# kachisys.net
KiCad netlist of a schematic drawn in EAGLE
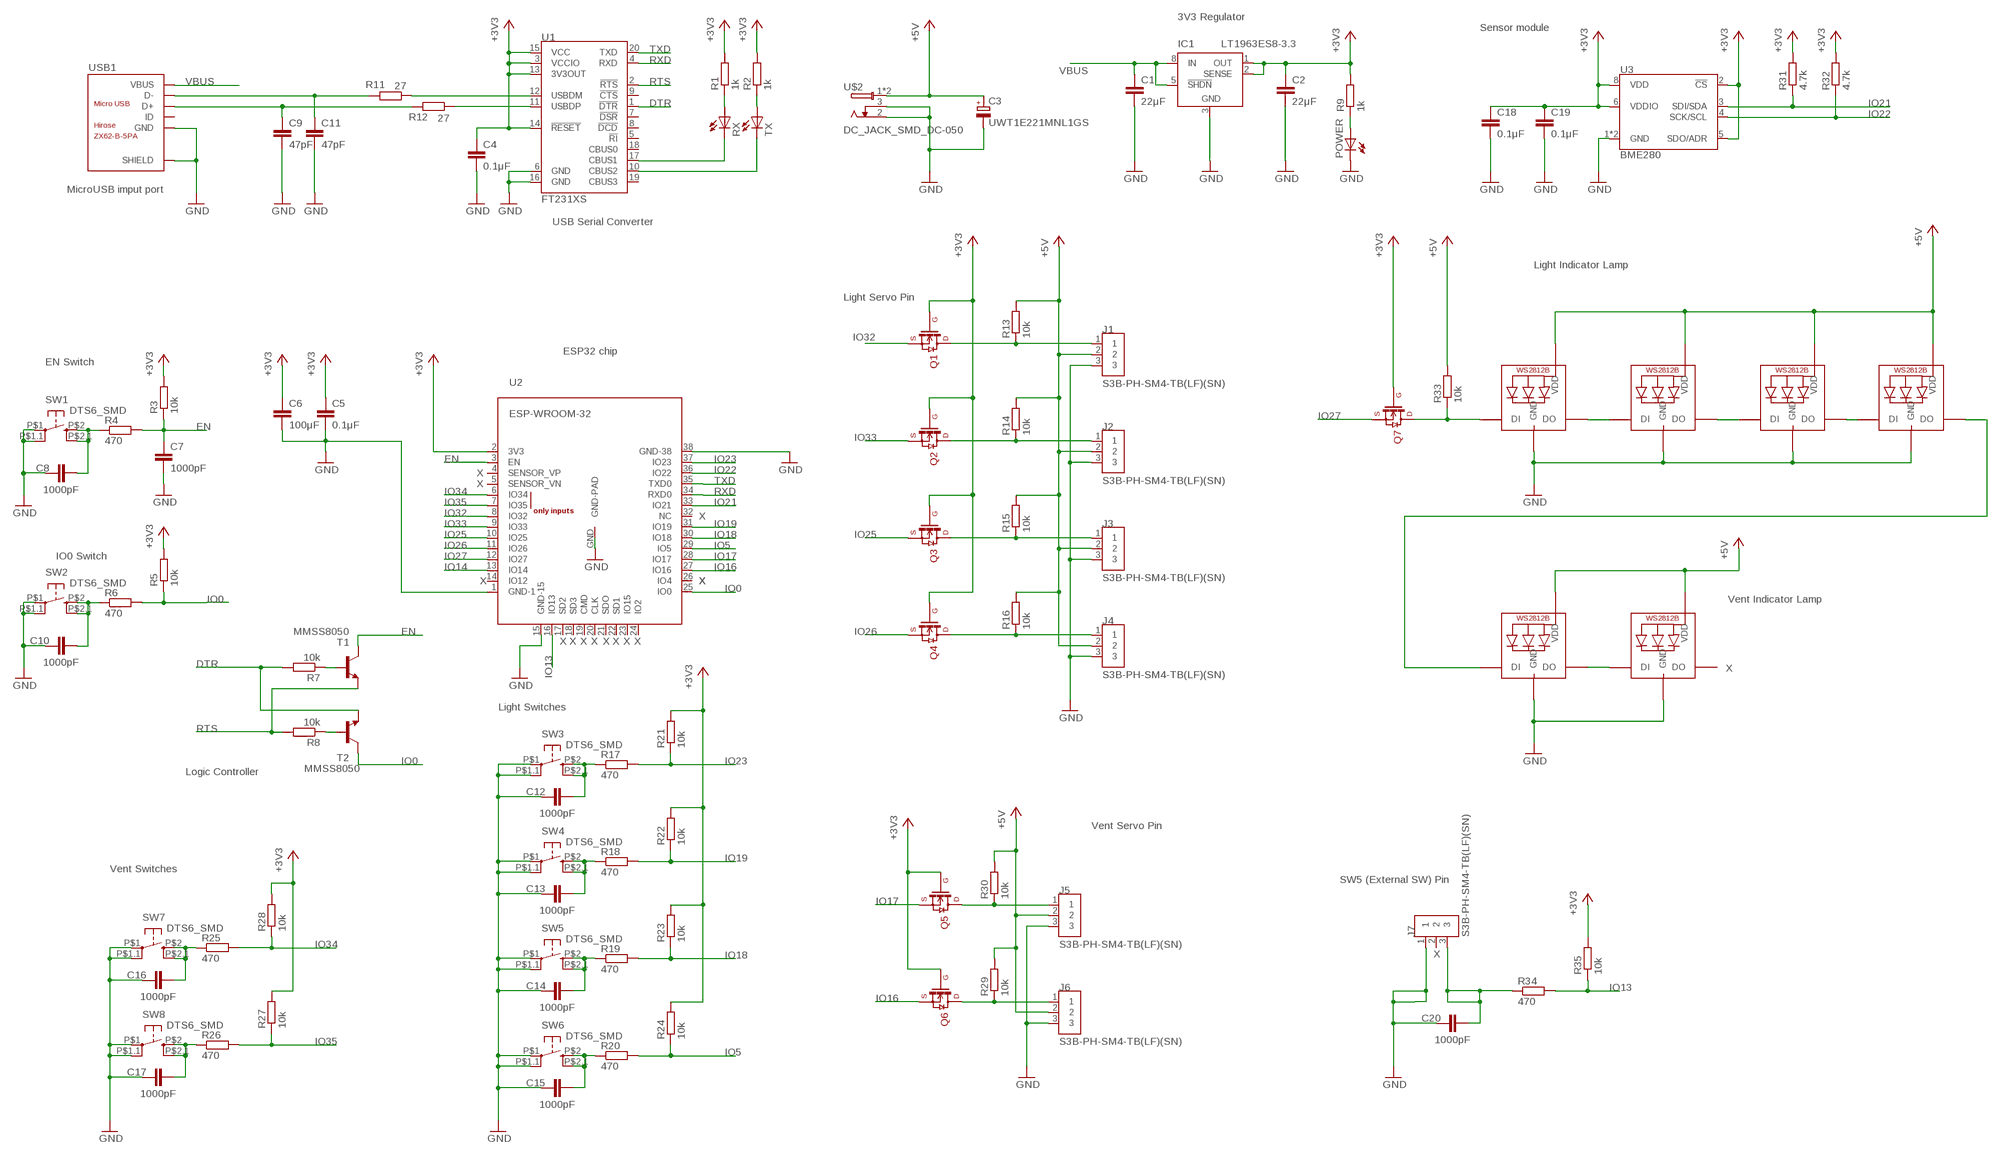
[diagram p0: schematic, sheet 1]

(export (version "E")
  (design (tool "Eeschema 10.0.6"))
  (components
    (comp (ref "C1")
      (value "22μF")
      (footprint "eagle-import:C2012")
      (libsource (lib "eagle-import") (part "resistor_348_C-EUC2012"))
    )
    (comp (ref "C2")
      (value "22μF")
      (footprint "eagle-import:C2012")
      (libsource (lib "eagle-import") (part "resistor_348_C-EUC2012"))
    )
    (comp (ref "C3")
      (value "UWT1E221MNL1GS")
      (footprint "eagle-import:NICHICON-ALMINUM-CAPACITOR-8MM")
      (libsource (lib "eagle-import") (part "UWT1E221MNL1GS"))
    )
    (comp (ref "C4")
      (value "0.1μF")
      (footprint "eagle-import:C0603")
      (libsource (lib "eagle-import") (part "resistor_348_C-EUC0603"))
    )
    (comp (ref "C5")
      (value "0.1μF")
      (footprint "eagle-import:C0603")
      (libsource (lib "eagle-import") (part "resistor_348_C-EUC0603"))
    )
    (comp (ref "C6")
      (value "100μF")
      (footprint "eagle-import:C3225")
      (libsource (lib "eagle-import") (part "resistor_348_C-EUC3225"))
    )
    (comp (ref "C7")
      (value "1000pF")
      (footprint "eagle-import:C0603")
      (libsource (lib "eagle-import") (part "resistor_348_C-EUC0603"))
    )
    (comp (ref "C8")
      (value "1000pF")
      (footprint "eagle-import:C0603")
      (libsource (lib "eagle-import") (part "resistor_348_C-EUC0603"))
    )
    (comp (ref "C9")
      (value "47pF")
      (footprint "eagle-import:C1608")
      (libsource (lib "eagle-import") (part "C-EUC1608"))
    )
    (comp (ref "C10")
      (value "1000pF")
      (footprint "eagle-import:C0603")
      (libsource (lib "eagle-import") (part "resistor_348_C-EUC0603"))
    )
    (comp (ref "C11")
      (value "47pF")
      (footprint "eagle-import:C1608")
      (libsource (lib "eagle-import") (part "C-EUC1608"))
    )
    (comp (ref "C12")
      (value "1000pF")
      (footprint "eagle-import:C0603")
      (libsource (lib "eagle-import") (part "resistor_348_C-EUC0603"))
    )
    (comp (ref "C13")
      (value "1000pF")
      (footprint "eagle-import:C0603")
      (libsource (lib "eagle-import") (part "resistor_348_C-EUC0603"))
    )
    (comp (ref "C14")
      (value "1000pF")
      (footprint "eagle-import:C0603")
      (libsource (lib "eagle-import") (part "resistor_348_C-EUC0603"))
    )
    (comp (ref "C15")
      (value "1000pF")
      (footprint "eagle-import:C0603")
      (libsource (lib "eagle-import") (part "resistor_348_C-EUC0603"))
    )
    (comp (ref "C16")
      (value "1000pF")
      (footprint "eagle-import:C0603")
      (libsource (lib "eagle-import") (part "resistor_348_C-EUC0603"))
    )
    (comp (ref "C17")
      (value "1000pF")
      (footprint "eagle-import:C0603")
      (libsource (lib "eagle-import") (part "resistor_348_C-EUC0603"))
    )
    (comp (ref "C18")
      (value "0.1μF")
      (footprint "eagle-import:C0603")
      (libsource (lib "eagle-import") (part "resistor_348_C-EUC0603"))
    )
    (comp (ref "C19")
      (value "0.1μF")
      (footprint "eagle-import:C0603")
      (libsource (lib "eagle-import") (part "resistor_348_C-EUC0603"))
    )
    (comp (ref "C20")
      (value "1000pF")
      (footprint "eagle-import:C0603")
      (libsource (lib "eagle-import") (part "resistor_348_C-EUC0603"))
    )
    (comp (ref "IC1")
      (value "LT1963ES8-3.3")
      (footprint "eagle-import:SOIC8")
      (libsource (lib "eagle-import") (part "LT1963ES8-3.3"))
    )
    (comp (ref "J1")
      (value "S3B-PH-SM4-TB(LF)(SN)")
      (footprint "eagle-import:JST_S3B-PH-SM4-TB(LF)(SN)")
      (fields
        (field (name "DIGI-KEY_PART_NUMBER") "455-1750-1-ND")
        (field (name "MF") "JST Sales")
        (field (name "MP") "S3B-PH-SM4-TB_LF__SN_")
      )
      (libsource (lib "eagle-import") (part "S3B-PH-SM4-TB(LF)(SN)"))
    )
    (comp (ref "J2")
      (value "S3B-PH-SM4-TB(LF)(SN)")
      (footprint "eagle-import:JST_S3B-PH-SM4-TB(LF)(SN)")
      (fields
        (field (name "DIGI-KEY_PART_NUMBER") "455-1750-1-ND")
        (field (name "MF") "JST Sales")
        (field (name "MP") "S3B-PH-SM4-TB_LF__SN_")
      )
      (libsource (lib "eagle-import") (part "S3B-PH-SM4-TB(LF)(SN)"))
    )
    (comp (ref "J3")
      (value "S3B-PH-SM4-TB(LF)(SN)")
      (footprint "eagle-import:JST_S3B-PH-SM4-TB(LF)(SN)")
      (fields
        (field (name "DIGI-KEY_PART_NUMBER") "455-1750-1-ND")
        (field (name "MF") "JST Sales")
        (field (name "MP") "S3B-PH-SM4-TB_LF__SN_")
      )
      (libsource (lib "eagle-import") (part "S3B-PH-SM4-TB(LF)(SN)"))
    )
    (comp (ref "J4")
      (value "S3B-PH-SM4-TB(LF)(SN)")
      (footprint "eagle-import:JST_S3B-PH-SM4-TB(LF)(SN)")
      (fields
        (field (name "DIGI-KEY_PART_NUMBER") "455-1750-1-ND")
        (field (name "MF") "JST Sales")
        (field (name "MP") "S3B-PH-SM4-TB_LF__SN_")
      )
      (libsource (lib "eagle-import") (part "S3B-PH-SM4-TB(LF)(SN)"))
    )
    (comp (ref "J5")
      (value "S3B-PH-SM4-TB(LF)(SN)")
      (footprint "eagle-import:JST_S3B-PH-SM4-TB(LF)(SN)")
      (fields
        (field (name "DIGI-KEY_PART_NUMBER") "455-1750-1-ND")
        (field (name "MF") "JST Sales")
        (field (name "MP") "S3B-PH-SM4-TB_LF__SN_")
      )
      (libsource (lib "eagle-import") (part "S3B-PH-SM4-TB(LF)(SN)"))
    )
    (comp (ref "J6")
      (value "S3B-PH-SM4-TB(LF)(SN)")
      (footprint "eagle-import:JST_S3B-PH-SM4-TB(LF)(SN)")
      (fields
        (field (name "DIGI-KEY_PART_NUMBER") "455-1750-1-ND")
        (field (name "MF") "JST Sales")
        (field (name "MP") "S3B-PH-SM4-TB_LF__SN_")
      )
      (libsource (lib "eagle-import") (part "S3B-PH-SM4-TB(LF)(SN)"))
    )
    (comp (ref "J7")
      (value "S3B-PH-SM4-TB(LF)(SN)")
      (footprint "eagle-import:JST_S3B-PH-SM4-TB(LF)(SN)")
      (fields
        (field (name "DIGI-KEY_PART_NUMBER") "455-1750-1-ND")
        (field (name "MF") "JST Sales")
        (field (name "MP") "S3B-PH-SM4-TB_LF__SN_")
      )
      (libsource (lib "eagle-import") (part "S3B-PH-SM4-TB(LF)(SN)"))
    )
    (comp (ref "LED1")
      (value "WS2812B_5050N")
      (footprint "eagle-import:WS2812B-NARROW")
      (libsource (lib "eagle-import") (part "WS2812B_5050N"))
    )
    (comp (ref "LED2")
      (value "WS2812B_5050N")
      (footprint "eagle-import:WS2812B-NARROW")
      (libsource (lib "eagle-import") (part "WS2812B_5050N"))
    )
    (comp (ref "LED3")
      (value "WS2812B_5050N")
      (footprint "eagle-import:WS2812B-NARROW")
      (libsource (lib "eagle-import") (part "WS2812B_5050N"))
    )
    (comp (ref "LED4")
      (value "WS2812B_5050N")
      (footprint "eagle-import:WS2812B-NARROW")
      (libsource (lib "eagle-import") (part "WS2812B_5050N"))
    )
    (comp (ref "LED5")
      (value "WS2812B_5050N")
      (footprint "eagle-import:WS2812B-NARROW")
      (libsource (lib "eagle-import") (part "WS2812B_5050N"))
    )
    (comp (ref "LED6")
      (value "WS2812B_5050N")
      (footprint "eagle-import:WS2812B-NARROW")
      (libsource (lib "eagle-import") (part "WS2812B_5050N"))
    )
    (comp (ref "POWER")
      (value "LEDCHIP-LED0603")
      (footprint "eagle-import:CHIP-LED0603")
      (libsource (lib "eagle-import") (part "LEDCHIP-LED0603"))
    )
    (comp (ref "Q1")
      (value "BSS138")
      (footprint "eagle-import:SOT-23")
      (libsource (lib "eagle-import") (part "BSS138"))
    )
    (comp (ref "Q2")
      (value "BSS138")
      (footprint "eagle-import:SOT-23")
      (libsource (lib "eagle-import") (part "BSS138"))
    )
    (comp (ref "Q3")
      (value "BSS138")
      (footprint "eagle-import:SOT-23")
      (libsource (lib "eagle-import") (part "BSS138"))
    )
    (comp (ref "Q4")
      (value "BSS138")
      (footprint "eagle-import:SOT-23")
      (libsource (lib "eagle-import") (part "BSS138"))
    )
    (comp (ref "Q5")
      (value "BSS138")
      (footprint "eagle-import:SOT-23")
      (libsource (lib "eagle-import") (part "BSS138"))
    )
    (comp (ref "Q6")
      (value "BSS138")
      (footprint "eagle-import:SOT-23")
      (libsource (lib "eagle-import") (part "BSS138"))
    )
    (comp (ref "Q7")
      (value "BSS138")
      (footprint "eagle-import:SOT-23")
      (libsource (lib "eagle-import") (part "BSS138"))
    )
    (comp (ref "R1")
      (value "1k")
      (footprint "eagle-import:R0603")
      (libsource (lib "eagle-import") (part "R-EU_R0603"))
    )
    (comp (ref "R2")
      (value "1k")
      (footprint "eagle-import:R0603")
      (libsource (lib "eagle-import") (part "R-EU_R0603"))
    )
    (comp (ref "R3")
      (value "10k")
      (footprint "eagle-import:R0603")
      (libsource (lib "eagle-import") (part "R-EU_R0603"))
    )
    (comp (ref "R4")
      (value "470")
      (footprint "eagle-import:R0603")
      (libsource (lib "eagle-import") (part "R-EU_R0603"))
    )
    (comp (ref "R5")
      (value "10k")
      (footprint "eagle-import:R0603")
      (libsource (lib "eagle-import") (part "R-EU_R0603"))
    )
    (comp (ref "R6")
      (value "470")
      (footprint "eagle-import:R0603")
      (libsource (lib "eagle-import") (part "R-EU_R0603"))
    )
    (comp (ref "R7")
      (value "10k")
      (footprint "eagle-import:R0603")
      (libsource (lib "eagle-import") (part "R-EU_R0603"))
    )
    (comp (ref "R8")
      (value "10k")
      (footprint "eagle-import:R0603")
      (libsource (lib "eagle-import") (part "R-EU_R0603"))
    )
    (comp (ref "R9")
      (value "1k")
      (footprint "eagle-import:R0603")
      (libsource (lib "eagle-import") (part "R-EU_R0603"))
    )
    (comp (ref "R11")
      (value "27")
      (footprint "eagle-import:R0603")
      (libsource (lib "eagle-import") (part "R-EU_R0603"))
    )
    (comp (ref "R12")
      (value "27")
      (footprint "eagle-import:R0603")
      (libsource (lib "eagle-import") (part "R-EU_R0603"))
    )
    (comp (ref "R13")
      (value "10k")
      (footprint "eagle-import:R0603")
      (libsource (lib "eagle-import") (part "R-EU_R0603"))
    )
    (comp (ref "R14")
      (value "10k")
      (footprint "eagle-import:R0603")
      (libsource (lib "eagle-import") (part "R-EU_R0603"))
    )
    (comp (ref "R15")
      (value "10k")
      (footprint "eagle-import:R0603")
      (libsource (lib "eagle-import") (part "R-EU_R0603"))
    )
    (comp (ref "R16")
      (value "10k")
      (footprint "eagle-import:R0603")
      (libsource (lib "eagle-import") (part "R-EU_R0603"))
    )
    (comp (ref "R17")
      (value "470")
      (footprint "eagle-import:R0603")
      (libsource (lib "eagle-import") (part "R-EU_R0603"))
    )
    (comp (ref "R18")
      (value "470")
      (footprint "eagle-import:R0603")
      (libsource (lib "eagle-import") (part "R-EU_R0603"))
    )
    (comp (ref "R19")
      (value "470")
      (footprint "eagle-import:R0603")
      (libsource (lib "eagle-import") (part "R-EU_R0603"))
    )
    (comp (ref "R20")
      (value "470")
      (footprint "eagle-import:R0603")
      (libsource (lib "eagle-import") (part "R-EU_R0603"))
    )
    (comp (ref "R21")
      (value "10k")
      (footprint "eagle-import:R0603")
      (libsource (lib "eagle-import") (part "R-EU_R0603"))
    )
    (comp (ref "R22")
      (value "10k")
      (footprint "eagle-import:R0603")
      (libsource (lib "eagle-import") (part "R-EU_R0603"))
    )
    (comp (ref "R23")
      (value "10k")
      (footprint "eagle-import:R0603")
      (libsource (lib "eagle-import") (part "R-EU_R0603"))
    )
    (comp (ref "R24")
      (value "10k")
      (footprint "eagle-import:R0603")
      (libsource (lib "eagle-import") (part "R-EU_R0603"))
    )
    (comp (ref "R25")
      (value "470")
      (footprint "eagle-import:R0603")
      (libsource (lib "eagle-import") (part "R-EU_R0603"))
    )
    (comp (ref "R26")
      (value "470")
      (footprint "eagle-import:R0603")
      (libsource (lib "eagle-import") (part "R-EU_R0603"))
    )
    (comp (ref "R27")
      (value "10k")
      (footprint "eagle-import:R0603")
      (libsource (lib "eagle-import") (part "R-EU_R0603"))
    )
    (comp (ref "R28")
      (value "10k")
      (footprint "eagle-import:R0603")
      (libsource (lib "eagle-import") (part "R-EU_R0603"))
    )
    (comp (ref "R29")
      (value "10k")
      (footprint "eagle-import:R0603")
      (libsource (lib "eagle-import") (part "R-EU_R0603"))
    )
    (comp (ref "R30")
      (value "10k")
      (footprint "eagle-import:R0603")
      (libsource (lib "eagle-import") (part "R-EU_R0603"))
    )
    (comp (ref "R31")
      (value "4.7k")
      (footprint "eagle-import:R0603")
      (libsource (lib "eagle-import") (part "R-EU_R0603"))
    )
    (comp (ref "R32")
      (value "4.7k")
      (footprint "eagle-import:R0603")
      (libsource (lib "eagle-import") (part "R-EU_R0603"))
    )
    (comp (ref "R33")
      (value "10k")
      (footprint "eagle-import:R0603")
      (libsource (lib "eagle-import") (part "R-EU_R0603"))
    )
    (comp (ref "R34")
      (value "470")
      (footprint "eagle-import:R0603")
      (libsource (lib "eagle-import") (part "R-EU_R0603"))
    )
    (comp (ref "R35")
      (value "10k")
      (footprint "eagle-import:R0603")
      (libsource (lib "eagle-import") (part "R-EU_R0603"))
    )
    (comp (ref "RX")
      (value "LEDCHIP-LED0603")
      (footprint "eagle-import:CHIP-LED0603")
      (libsource (lib "eagle-import") (part "LEDCHIP-LED0603"))
    )
    (comp (ref "SW1")
      (value "DTS6_SMD")
      (footprint "eagle-import:SKRPACE010")
      (libsource (lib "eagle-import") (part "DTS6_SMD"))
    )
    (comp (ref "SW2")
      (value "DTS6_SMD")
      (footprint "eagle-import:SKRPACE010")
      (libsource (lib "eagle-import") (part "DTS6_SMD"))
    )
    (comp (ref "SW3")
      (value "DTS6_SMD")
      (footprint "eagle-import:SKRPACE010")
      (libsource (lib "eagle-import") (part "DTS6_SMD"))
    )
    (comp (ref "SW4")
      (value "DTS6_SMD")
      (footprint "eagle-import:SKRPACE010")
      (libsource (lib "eagle-import") (part "DTS6_SMD"))
    )
    (comp (ref "SW5")
      (value "DTS6_SMD")
      (footprint "eagle-import:SKRPACE010")
      (libsource (lib "eagle-import") (part "DTS6_SMD"))
    )
    (comp (ref "SW6")
      (value "DTS6_SMD")
      (footprint "eagle-import:SKRPACE010")
      (libsource (lib "eagle-import") (part "DTS6_SMD"))
    )
    (comp (ref "SW7")
      (value "DTS6_SMD")
      (footprint "eagle-import:SKRPACE010")
      (libsource (lib "eagle-import") (part "DTS6_SMD"))
    )
    (comp (ref "SW8")
      (value "DTS6_SMD")
      (footprint "eagle-import:SKRPACE010")
      (libsource (lib "eagle-import") (part "DTS6_SMD"))
    )
    (comp (ref "T1")
      (value "MMSS8050")
      (footprint "eagle-import:SOT23-EBC")
      (libsource (lib "eagle-import") (part "-NPN-SOT23-EBC"))
    )
    (comp (ref "T2")
      (value "MMSS8050")
      (footprint "eagle-import:SOT23-EBC")
      (libsource (lib "eagle-import") (part "-NPN-SOT23-EBC"))
    )
    (comp (ref "TX")
      (value "LEDCHIP-LED0603")
      (footprint "eagle-import:CHIP-LED0603")
      (libsource (lib "eagle-import") (part "LEDCHIP-LED0603"))
    )
    (comp (ref "U$2")
      (value "DC_JACK_SMD_DC-050")
      (footprint "eagle-import:DC_JACK_SMD_DC-050")
      (libsource (lib "eagle-import") (part "DC_JACK_SMD_DC-050"))
    )
    (comp (ref "U1")
      (value "FT231XS")
      (footprint "eagle-import:SSOP20_L")
      (libsource (lib "eagle-import") (part "FT231XS"))
    )
    (comp (ref "U2")
      (value "ESP-WROOM-32")
      (footprint "eagle-import:ESP-WROOM-32")
      (libsource (lib "eagle-import") (part "ESP-WROOM-32"))
    )
    (comp (ref "U3")
      (value "BME280")
      (footprint "eagle-import:LGA-8-2.5X2.5")
      (libsource (lib "eagle-import") (part "BME280"))
    )
    (comp (ref "USB1")
      (value "ZX62-B-5PA")
      (footprint "eagle-import:MICRO-USB5+6P-SMD-0.65-AB")
      (libsource (lib "eagle-import") (part "MICRO-USB-SMD(ZX62-B-5PA)"))
    )
  )
  (nets
    (net (code "1") (name "+3V3") (class "Default")
      (node (ref "C18") (pin "1") (pinfunction "1_1") (pintype "passive"))
      (node (ref "C19") (pin "1") (pinfunction "1_1") (pintype "passive"))
      (node (ref "C2") (pin "1") (pinfunction "1_1") (pintype "passive"))
      (node (ref "C4") (pin "1") (pinfunction "1_1") (pintype "passive"))
      (node (ref "C5") (pin "1") (pinfunction "1_1") (pintype "passive"))
      (node (ref "C6") (pin "1") (pinfunction "1_1") (pintype "passive"))
      (node (ref "IC1") (pin "1") (pinfunction "OUT_1") (pintype "output"))
      (node (ref "IC1") (pin "2") (pinfunction "SENSE_2") (pintype "input"))
      (node (ref "Q1") (pin "G") (pinfunction "G_G") (pintype "passive"))
      (node (ref "Q2") (pin "G") (pinfunction "G_G") (pintype "passive"))
      (node (ref "Q3") (pin "G") (pinfunction "G_G") (pintype "passive"))
      (node (ref "Q4") (pin "G") (pinfunction "G_G") (pintype "passive"))
      (node (ref "Q5") (pin "G") (pinfunction "G_G") (pintype "passive"))
      (node (ref "Q6") (pin "G") (pinfunction "G_G") (pintype "passive"))
      (node (ref "Q7") (pin "G") (pinfunction "G_G") (pintype "passive"))
      (node (ref "R1") (pin "2") (pinfunction "2_2") (pintype "passive"))
      (node (ref "R2") (pin "2") (pinfunction "2_2") (pintype "passive"))
      (node (ref "R21") (pin "2") (pinfunction "2_2") (pintype "passive"))
      (node (ref "R22") (pin "2") (pinfunction "2_2") (pintype "passive"))
      (node (ref "R23") (pin "2") (pinfunction "2_2") (pintype "passive"))
      (node (ref "R24") (pin "2") (pinfunction "2_2") (pintype "passive"))
      (node (ref "R27") (pin "2") (pinfunction "2_2") (pintype "passive"))
      (node (ref "R28") (pin "2") (pinfunction "2_2") (pintype "passive"))
      (node (ref "R3") (pin "2") (pinfunction "2_2") (pintype "passive"))
      (node (ref "R31") (pin "2") (pinfunction "2_2") (pintype "passive"))
      (node (ref "R32") (pin "2") (pinfunction "2_2") (pintype "passive"))
      (node (ref "R35") (pin "2") (pinfunction "2_2") (pintype "passive"))
      (node (ref "R5") (pin "2") (pinfunction "2_2") (pintype "passive"))
      (node (ref "R9") (pin "2") (pinfunction "2_2") (pintype "passive"))
      (node (ref "U1") (pin "13") (pinfunction "3V3OUT_13") (pintype "bidirectional"))
      (node (ref "U1") (pin "14") (pinfunction "~{RESET}_14") (pintype "bidirectional"))
      (node (ref "U1") (pin "15") (pinfunction "VCC_15") (pintype "bidirectional"))
      (node (ref "U1") (pin "3") (pinfunction "VCCIO_3") (pintype "bidirectional"))
      (node (ref "U2") (pin "2") (pinfunction "3V3_2") (pintype "bidirectional"))
      (node (ref "U3") (pin "2") (pinfunction "~{CS}_2") (pintype "bidirectional"))
      (node (ref "U3") (pin "5") (pinfunction "SDO/ADR_5") (pintype "bidirectional"))
      (node (ref "U3") (pin "6") (pinfunction "VDDIO_6") (pintype "bidirectional"))
      (node (ref "U3") (pin "8") (pinfunction "VDD_8") (pintype "bidirectional"))
    )
    (net (code "2") (name "+5V") (class "Default")
      (node (ref "C3") (pin "POS") (pinfunction "+_POS") (pintype "passive"))
      (node (ref "J1") (pin "2") (pinfunction "2_2") (pintype "passive"))
      (node (ref "J2") (pin "2") (pinfunction "2_2") (pintype "passive"))
      (node (ref "J3") (pin "2") (pinfunction "2_2") (pintype "passive"))
      (node (ref "J4") (pin "2") (pinfunction "2_2") (pintype "passive"))
      (node (ref "J5") (pin "2") (pinfunction "2_2") (pintype "passive"))
      (node (ref "J6") (pin "2") (pinfunction "2_2") (pintype "passive"))
      (node (ref "LED1") (pin "1-VDD") (pinfunction "VDD_1-VDD") (pintype "power_in"))
      (node (ref "LED2") (pin "1-VDD") (pinfunction "VDD_1-VDD") (pintype "power_in"))
      (node (ref "LED3") (pin "1-VDD") (pinfunction "VDD_1-VDD") (pintype "power_in"))
      (node (ref "LED4") (pin "1-VDD") (pinfunction "VDD_1-VDD") (pintype "power_in"))
      (node (ref "LED5") (pin "1-VDD") (pinfunction "VDD_1-VDD") (pintype "power_in"))
      (node (ref "LED6") (pin "1-VDD") (pinfunction "VDD_1-VDD") (pintype "power_in"))
      (node (ref "R13") (pin "2") (pinfunction "2_2") (pintype "passive"))
      (node (ref "R14") (pin "2") (pinfunction "2_2") (pintype "passive"))
      (node (ref "R15") (pin "2") (pinfunction "2_2") (pintype "passive"))
      (node (ref "R16") (pin "2") (pinfunction "2_2") (pintype "passive"))
      (node (ref "R29") (pin "2") (pinfunction "2_2") (pintype "passive"))
      (node (ref "R30") (pin "2") (pinfunction "2_2") (pintype "passive"))
      (node (ref "R33") (pin "2") (pinfunction "2_2") (pintype "passive"))
      (node (ref "U$2") (pin "1") (pinfunction "1_1") (pintype "passive"))
      (node (ref "U$2") (pin "1-1") (pinfunction "1_1-1") (pintype "passive"))
    )
    (net (code "3") (name "/DTR") (class "Default")
      (node (ref "R7") (pin "2") (pinfunction "2_2") (pintype "passive"))
      (node (ref "T2") (pin "E") (pinfunction "E_E") (pintype "passive"))
      (node (ref "U1") (pin "1") (pinfunction "~{DTR}_1") (pintype "bidirectional"))
    )
    (net (code "4") (name "/EN") (class "Default")
      (node (ref "C7") (pin "1") (pinfunction "1_1") (pintype "passive"))
      (node (ref "R3") (pin "1") (pinfunction "1_1") (pintype "passive"))
      (node (ref "R4") (pin "2") (pinfunction "2_2") (pintype "passive"))
      (node (ref "T1") (pin "C") (pinfunction "C_C") (pintype "passive"))
      (node (ref "U2") (pin "3") (pinfunction "EN_3") (pintype "bidirectional"))
    )
    (net (code "5") (name "/IO0") (class "Default")
      (node (ref "R5") (pin "1") (pinfunction "1_1") (pintype "passive"))
      (node (ref "R6") (pin "2") (pinfunction "2_2") (pintype "passive"))
      (node (ref "T2") (pin "C") (pinfunction "C_C") (pintype "passive"))
      (node (ref "U2") (pin "25") (pinfunction "IO0_25") (pintype "bidirectional"))
    )
    (net (code "6") (name "/IO5") (class "Default")
      (node (ref "R20") (pin "2") (pinfunction "2_2") (pintype "passive"))
      (node (ref "R24") (pin "1") (pinfunction "1_1") (pintype "passive"))
      (node (ref "U2") (pin "29") (pinfunction "IO5_29") (pintype "bidirectional"))
    )
    (net (code "7") (name "/IO13") (class "Default")
      (node (ref "R34") (pin "2") (pinfunction "2_2") (pintype "passive"))
      (node (ref "R35") (pin "1") (pinfunction "1_1") (pintype "passive"))
      (node (ref "U2") (pin "16") (pinfunction "IO13_16") (pintype "bidirectional"))
    )
    (net (code "8") (name "/IO14") (class "Default")
      (node (ref "U2") (pin "13") (pinfunction "IO14_13") (pintype "bidirectional"))
    )
    (net (code "9") (name "/IO16") (class "Default")
      (node (ref "Q6") (pin "S") (pinfunction "S_S") (pintype "passive"))
      (node (ref "U2") (pin "27") (pinfunction "IO16_27") (pintype "bidirectional"))
    )
    (net (code "10") (name "/IO17") (class "Default")
      (node (ref "Q5") (pin "S") (pinfunction "S_S") (pintype "passive"))
      (node (ref "U2") (pin "28") (pinfunction "IO17_28") (pintype "bidirectional"))
    )
    (net (code "11") (name "/IO18") (class "Default")
      (node (ref "R19") (pin "2") (pinfunction "2_2") (pintype "passive"))
      (node (ref "R23") (pin "1") (pinfunction "1_1") (pintype "passive"))
      (node (ref "U2") (pin "30") (pinfunction "IO18_30") (pintype "bidirectional"))
    )
    (net (code "12") (name "/IO19") (class "Default")
      (node (ref "R18") (pin "2") (pinfunction "2_2") (pintype "passive"))
      (node (ref "R22") (pin "1") (pinfunction "1_1") (pintype "passive"))
      (node (ref "U2") (pin "31") (pinfunction "IO19_31") (pintype "bidirectional"))
    )
    (net (code "13") (name "/IO21") (class "Default")
      (node (ref "R31") (pin "1") (pinfunction "1_1") (pintype "passive"))
      (node (ref "U2") (pin "33") (pinfunction "IO21_33") (pintype "bidirectional"))
      (node (ref "U3") (pin "3") (pinfunction "SDI/SDA_3") (pintype "bidirectional"))
    )
    (net (code "14") (name "/IO22") (class "Default")
      (node (ref "R32") (pin "1") (pinfunction "1_1") (pintype "passive"))
      (node (ref "U2") (pin "36") (pinfunction "IO22_36") (pintype "bidirectional"))
      (node (ref "U3") (pin "4") (pinfunction "SCK/SCL_4") (pintype "bidirectional"))
    )
    (net (code "15") (name "/IO23") (class "Default")
      (node (ref "R17") (pin "2") (pinfunction "2_2") (pintype "passive"))
      (node (ref "R21") (pin "1") (pinfunction "1_1") (pintype "passive"))
      (node (ref "U2") (pin "37") (pinfunction "IO23_37") (pintype "bidirectional"))
    )
    (net (code "16") (name "/IO25") (class "Default")
      (node (ref "Q3") (pin "S") (pinfunction "S_S") (pintype "passive"))
      (node (ref "U2") (pin "10") (pinfunction "IO25_10") (pintype "bidirectional"))
    )
    (net (code "17") (name "/IO26") (class "Default")
      (node (ref "Q4") (pin "S") (pinfunction "S_S") (pintype "passive"))
      (node (ref "U2") (pin "11") (pinfunction "IO26_11") (pintype "bidirectional"))
    )
    (net (code "18") (name "/IO27") (class "Default")
      (node (ref "Q7") (pin "S") (pinfunction "S_S") (pintype "passive"))
      (node (ref "U2") (pin "12") (pinfunction "IO27_12") (pintype "bidirectional"))
    )
    (net (code "19") (name "/IO32") (class "Default")
      (node (ref "Q1") (pin "S") (pinfunction "S_S") (pintype "passive"))
      (node (ref "U2") (pin "8") (pinfunction "IO32_8") (pintype "bidirectional"))
    )
    (net (code "20") (name "/IO33") (class "Default")
      (node (ref "Q2") (pin "S") (pinfunction "S_S") (pintype "passive"))
      (node (ref "U2") (pin "9") (pinfunction "IO33_9") (pintype "bidirectional"))
    )
    (net (code "21") (name "/IO34") (class "Default")
      (node (ref "R25") (pin "2") (pinfunction "2_2") (pintype "passive"))
      (node (ref "R28") (pin "1") (pinfunction "1_1") (pintype "passive"))
      (node (ref "U2") (pin "6") (pinfunction "IO34_6") (pintype "input"))
    )
    (net (code "22") (name "/IO35") (class "Default")
      (node (ref "R26") (pin "2") (pinfunction "2_2") (pintype "passive"))
      (node (ref "R27") (pin "1") (pinfunction "1_1") (pintype "passive"))
      (node (ref "U2") (pin "7") (pinfunction "IO35_7") (pintype "input"))
    )
    (net (code "23") (name "/RTS") (class "Default")
      (node (ref "R8") (pin "2") (pinfunction "2_2") (pintype "passive"))
      (node (ref "T1") (pin "E") (pinfunction "E_E") (pintype "passive"))
      (node (ref "U1") (pin "2") (pinfunction "~{RTS}_2") (pintype "bidirectional"))
    )
    (net (code "24") (name "/RXD") (class "Default")
      (node (ref "U1") (pin "4") (pinfunction "RXD_4") (pintype "bidirectional"))
      (node (ref "U2") (pin "34") (pinfunction "RXD0_34") (pintype "bidirectional"))
    )
    (net (code "25") (name "/TXD") (class "Default")
      (node (ref "U1") (pin "20") (pinfunction "TXD_20") (pintype "bidirectional"))
      (node (ref "U2") (pin "35") (pinfunction "TXD0_35") (pintype "bidirectional"))
    )
    (net (code "26") (name "/VBUS") (class "Default")
      (node (ref "C1") (pin "1") (pinfunction "1_1") (pintype "passive"))
      (node (ref "IC1") (pin "5") (pinfunction "~{SHDN}_5") (pintype "input"))
      (node (ref "IC1") (pin "8") (pinfunction "IN_8") (pintype "input"))
      (node (ref "USB1") (pin "1") (pinfunction "VBUS_1") (pintype "power_in"))
    )
    (net (code "27") (name "GND") (class "Default")
      (node (ref "C1") (pin "2") (pinfunction "2_2") (pintype "passive"))
      (node (ref "C10") (pin "1") (pinfunction "1_1") (pintype "passive"))
      (node (ref "C11") (pin "2") (pinfunction "2_2") (pintype "passive"))
      (node (ref "C12") (pin "1") (pinfunction "1_1") (pintype "passive"))
      (node (ref "C13") (pin "1") (pinfunction "1_1") (pintype "passive"))
      (node (ref "C14") (pin "1") (pinfunction "1_1") (pintype "passive"))
      (node (ref "C15") (pin "1") (pinfunction "1_1") (pintype "passive"))
      (node (ref "C16") (pin "1") (pinfunction "1_1") (pintype "passive"))
      (node (ref "C17") (pin "1") (pinfunction "1_1") (pintype "passive"))
      (node (ref "C18") (pin "2") (pinfunction "2_2") (pintype "passive"))
      (node (ref "C19") (pin "2") (pinfunction "2_2") (pintype "passive"))
      (node (ref "C2") (pin "2") (pinfunction "2_2") (pintype "passive"))
      (node (ref "C20") (pin "1") (pinfunction "1_1") (pintype "passive"))
      (node (ref "C3") (pin "NEG") (pinfunction "-_NEG") (pintype "passive"))
      (node (ref "C4") (pin "2") (pinfunction "2_2") (pintype "passive"))
      (node (ref "C5") (pin "2") (pinfunction "2_2") (pintype "passive"))
      (node (ref "C6") (pin "2") (pinfunction "2_2") (pintype "passive"))
      (node (ref "C7") (pin "2") (pinfunction "2_2") (pintype "passive"))
      (node (ref "C8") (pin "1") (pinfunction "1_1") (pintype "passive"))
      (node (ref "C9") (pin "2") (pinfunction "2_2") (pintype "passive"))
      (node (ref "IC1") (pin "3") (pinfunction "GND_3") (pintype "power_in"))
      (node (ref "J1") (pin "3") (pinfunction "3_3") (pintype "passive"))
      (node (ref "J2") (pin "3") (pinfunction "3_3") (pintype "passive"))
      (node (ref "J3") (pin "3") (pinfunction "3_3") (pintype "passive"))
      (node (ref "J4") (pin "3") (pinfunction "3_3") (pintype "passive"))
      (node (ref "J5") (pin "3") (pinfunction "3_3") (pintype "passive"))
      (node (ref "J6") (pin "3") (pinfunction "3_3") (pintype "passive"))
      (node (ref "J7") (pin "1") (pinfunction "1_1") (pintype "passive"))
      (node (ref "LED1") (pin "3-GND") (pinfunction "GND_3-GND") (pintype "power_in"))
      (node (ref "LED2") (pin "3-GND") (pinfunction "GND_3-GND") (pintype "power_in"))
      (node (ref "LED3") (pin "3-GND") (pinfunction "GND_3-GND") (pintype "power_in"))
      (node (ref "LED4") (pin "3-GND") (pinfunction "GND_3-GND") (pintype "power_in"))
      (node (ref "LED5") (pin "3-GND") (pinfunction "GND_3-GND") (pintype "power_in"))
      (node (ref "LED6") (pin "3-GND") (pinfunction "GND_3-GND") (pintype "power_in"))
      (node (ref "POWER") (pin "C") (pinfunction "C_C") (pintype "passive"))
      (node (ref "SW1") (pin "P$1") (pinfunction "P_P$1") (pintype "passive"))
      (node (ref "SW1") (pin "P$1.1") (pinfunction "P1_P$1.1") (pintype "passive"))
      (node (ref "SW2") (pin "P$1") (pinfunction "P_P$1") (pintype "passive"))
      (node (ref "SW2") (pin "P$1.1") (pinfunction "P1_P$1.1") (pintype "passive"))
      (node (ref "SW3") (pin "P$1") (pinfunction "P_P$1") (pintype "passive"))
      (node (ref "SW3") (pin "P$1.1") (pinfunction "P1_P$1.1") (pintype "passive"))
      (node (ref "SW4") (pin "P$1") (pinfunction "P_P$1") (pintype "passive"))
      (node (ref "SW4") (pin "P$1.1") (pinfunction "P1_P$1.1") (pintype "passive"))
      (node (ref "SW5") (pin "P$1") (pinfunction "P_P$1") (pintype "passive"))
      (node (ref "SW5") (pin "P$1.1") (pinfunction "P1_P$1.1") (pintype "passive"))
      (node (ref "SW6") (pin "P$1") (pinfunction "P_P$1") (pintype "passive"))
      (node (ref "SW6") (pin "P$1.1") (pinfunction "P1_P$1.1") (pintype "passive"))
      (node (ref "SW7") (pin "P$1") (pinfunction "P_P$1") (pintype "passive"))
      (node (ref "SW7") (pin "P$1.1") (pinfunction "P1_P$1.1") (pintype "passive"))
      (node (ref "SW8") (pin "P$1") (pinfunction "P_P$1") (pintype "passive"))
      (node (ref "SW8") (pin "P$1.1") (pinfunction "P1_P$1.1") (pintype "passive"))
      (node (ref "U$2") (pin "2") (pinfunction "2_2") (pintype "passive"))
      (node (ref "U$2") (pin "3") (pinfunction "3_3") (pintype "passive"))
      (node (ref "U1") (pin "16") (pinfunction "GND_16") (pintype "bidirectional"))
      (node (ref "U1") (pin "6") (pinfunction "GND_6") (pintype "bidirectional"))
      (node (ref "U2") (pin "1") (pinfunction "GND-1_1") (pintype "bidirectional"))
      (node (ref "U2") (pin "15") (pinfunction "GND-15_15") (pintype "bidirectional"))
      (node (ref "U2") (pin "38") (pinfunction "GND-38_38") (pintype "bidirectional"))
      (node (ref "U2") (pin "GND") (pinfunction "GND-PAD_GND") (pintype "bidirectional"))
      (node (ref "U3") (pin "1") (pinfunction "GND_1") (pintype "bidirectional"))
      (node (ref "U3") (pin "7") (pinfunction "GND_7") (pintype "bidirectional"))
      (node (ref "USB1") (pin "5") (pinfunction "GND_5") (pintype "power_in"))
      (node (ref "USB1") (pin "P1") (pinfunction "SHIELD_P1") (pintype "power_in"))
      (node (ref "USB1") (pin "P2") (pinfunction "SHIELD_P2") (pintype "power_in"))
      (node (ref "USB1") (pin "P3") (pinfunction "SHIELD_P3") (pintype "power_in"))
      (node (ref "USB1") (pin "P4") (pinfunction "SHIELD_P4") (pintype "power_in"))
      (node (ref "USB1") (pin "P5") (pinfunction "SHIELD_P5") (pintype "power_in"))
      (node (ref "USB1") (pin "P6") (pinfunction "SHIELD_P6") (pintype "power_in"))
    )
    (net (code "28") (name "Net-(C20-Pad2)") (class "Default")
      (node (ref "C20") (pin "2") (pinfunction "2_2") (pintype "passive"))
      (node (ref "J7") (pin "3") (pinfunction "3_3") (pintype "passive"))
      (node (ref "R34") (pin "1") (pinfunction "1_1") (pintype "passive"))
    )
    (net (code "29") (name "Net-(J1-Pad1)") (class "Default")
      (node (ref "J1") (pin "1") (pinfunction "1_1") (pintype "passive"))
      (node (ref "Q1") (pin "D") (pinfunction "D_D") (pintype "passive"))
      (node (ref "R13") (pin "1") (pinfunction "1_1") (pintype "passive"))
    )
    (net (code "30") (name "Net-(J2-Pad1)") (class "Default")
      (node (ref "J2") (pin "1") (pinfunction "1_1") (pintype "passive"))
      (node (ref "Q2") (pin "D") (pinfunction "D_D") (pintype "passive"))
      (node (ref "R14") (pin "1") (pinfunction "1_1") (pintype "passive"))
    )
    (net (code "31") (name "Net-(J3-Pad1)") (class "Default")
      (node (ref "J3") (pin "1") (pinfunction "1_1") (pintype "passive"))
      (node (ref "Q3") (pin "D") (pinfunction "D_D") (pintype "passive"))
      (node (ref "R15") (pin "1") (pinfunction "1_1") (pintype "passive"))
    )
    (net (code "32") (name "Net-(J4-Pad1)") (class "Default")
      (node (ref "J4") (pin "1") (pinfunction "1_1") (pintype "passive"))
      (node (ref "Q4") (pin "D") (pinfunction "D_D") (pintype "passive"))
      (node (ref "R16") (pin "1") (pinfunction "1_1") (pintype "passive"))
    )
    (net (code "33") (name "Net-(J5-Pad1)") (class "Default")
      (node (ref "J5") (pin "1") (pinfunction "1_1") (pintype "passive"))
      (node (ref "Q5") (pin "D") (pinfunction "D_D") (pintype "passive"))
      (node (ref "R30") (pin "1") (pinfunction "1_1") (pintype "passive"))
    )
    (net (code "34") (name "Net-(J6-Pad1)") (class "Default")
      (node (ref "J6") (pin "1") (pinfunction "1_1") (pintype "passive"))
      (node (ref "Q6") (pin "D") (pinfunction "D_D") (pintype "passive"))
      (node (ref "R29") (pin "1") (pinfunction "1_1") (pintype "passive"))
    )
    (net (code "35") (name "Net-(LED1-DI)") (class "Default")
      (node (ref "LED1") (pin "4-DIN") (pinfunction "DI_4-DIN") (pintype "input"))
      (node (ref "Q7") (pin "D") (pinfunction "D_D") (pintype "passive"))
      (node (ref "R33") (pin "1") (pinfunction "1_1") (pintype "passive"))
    )
    (net (code "36") (name "Net-(LED1-DO)") (class "Default")
      (node (ref "LED1") (pin "2-DOUT") (pinfunction "DO_2-DOUT") (pintype "output"))
      (node (ref "LED2") (pin "4-DIN") (pinfunction "DI_4-DIN") (pintype "input"))
    )
    (net (code "37") (name "Net-(LED2-DO)") (class "Default")
      (node (ref "LED2") (pin "2-DOUT") (pinfunction "DO_2-DOUT") (pintype "output"))
      (node (ref "LED3") (pin "4-DIN") (pinfunction "DI_4-DIN") (pintype "input"))
    )
    (net (code "38") (name "Net-(LED3-DO)") (class "Default")
      (node (ref "LED3") (pin "2-DOUT") (pinfunction "DO_2-DOUT") (pintype "output"))
      (node (ref "LED4") (pin "4-DIN") (pinfunction "DI_4-DIN") (pintype "input"))
    )
    (net (code "39") (name "Net-(LED4-DO)") (class "Default")
      (node (ref "LED4") (pin "2-DOUT") (pinfunction "DO_2-DOUT") (pintype "output"))
      (node (ref "LED5") (pin "4-DIN") (pinfunction "DI_4-DIN") (pintype "input"))
    )
    (net (code "40") (name "Net-(LED5-DO)") (class "Default")
      (node (ref "LED5") (pin "2-DOUT") (pinfunction "DO_2-DOUT") (pintype "output"))
      (node (ref "LED6") (pin "4-DIN") (pinfunction "DI_4-DIN") (pintype "input"))
    )
    (net (code "41") (name "Net-(POWER-PadA)") (class "Default")
      (node (ref "POWER") (pin "A") (pinfunction "A_A") (pintype "passive"))
      (node (ref "R9") (pin "1") (pinfunction "1_1") (pintype "passive"))
    )
    (net (code "42") (name "Net-(R1-Pad1)") (class "Default")
      (node (ref "R1") (pin "1") (pinfunction "1_1") (pintype "passive"))
      (node (ref "RX") (pin "A") (pinfunction "A_A") (pintype "passive"))
    )
    (net (code "43") (name "Net-(R2-Pad1)") (class "Default")
      (node (ref "R2") (pin "1") (pinfunction "1_1") (pintype "passive"))
      (node (ref "TX") (pin "A") (pinfunction "A_A") (pintype "passive"))
    )
    (net (code "44") (name "Net-(R7-Pad1)") (class "Default")
      (node (ref "R7") (pin "1") (pinfunction "1_1") (pintype "passive"))
      (node (ref "T1") (pin "B") (pinfunction "B_B") (pintype "passive"))
    )
    (net (code "45") (name "Net-(R8-Pad1)") (class "Default")
      (node (ref "R8") (pin "1") (pinfunction "1_1") (pintype "passive"))
      (node (ref "T2") (pin "B") (pinfunction "B_B") (pintype "passive"))
    )
    (net (code "46") (name "Net-(SW1-S)") (class "Default")
      (node (ref "C8") (pin "2") (pinfunction "2_2") (pintype "passive"))
      (node (ref "R4") (pin "1") (pinfunction "1_1") (pintype "passive"))
      (node (ref "SW1") (pin "P$2") (pinfunction "S_P$2") (pintype "passive"))
      (node (ref "SW1") (pin "P$2.1") (pinfunction "S1_P$2.1") (pintype "passive"))
    )
    (net (code "47") (name "Net-(SW2-S)") (class "Default")
      (node (ref "C10") (pin "2") (pinfunction "2_2") (pintype "passive"))
      (node (ref "R6") (pin "1") (pinfunction "1_1") (pintype "passive"))
      (node (ref "SW2") (pin "P$2") (pinfunction "S_P$2") (pintype "passive"))
      (node (ref "SW2") (pin "P$2.1") (pinfunction "S1_P$2.1") (pintype "passive"))
    )
    (net (code "48") (name "Net-(SW3-S)") (class "Default")
      (node (ref "C12") (pin "2") (pinfunction "2_2") (pintype "passive"))
      (node (ref "R17") (pin "1") (pinfunction "1_1") (pintype "passive"))
      (node (ref "SW3") (pin "P$2") (pinfunction "S_P$2") (pintype "passive"))
      (node (ref "SW3") (pin "P$2.1") (pinfunction "S1_P$2.1") (pintype "passive"))
    )
    (net (code "49") (name "Net-(SW4-S)") (class "Default")
      (node (ref "C13") (pin "2") (pinfunction "2_2") (pintype "passive"))
      (node (ref "R18") (pin "1") (pinfunction "1_1") (pintype "passive"))
      (node (ref "SW4") (pin "P$2") (pinfunction "S_P$2") (pintype "passive"))
      (node (ref "SW4") (pin "P$2.1") (pinfunction "S1_P$2.1") (pintype "passive"))
    )
    (net (code "50") (name "Net-(SW5-S)") (class "Default")
      (node (ref "C14") (pin "2") (pinfunction "2_2") (pintype "passive"))
      (node (ref "R19") (pin "1") (pinfunction "1_1") (pintype "passive"))
      (node (ref "SW5") (pin "P$2") (pinfunction "S_P$2") (pintype "passive"))
      (node (ref "SW5") (pin "P$2.1") (pinfunction "S1_P$2.1") (pintype "passive"))
    )
    (net (code "51") (name "Net-(SW6-S)") (class "Default")
      (node (ref "C15") (pin "2") (pinfunction "2_2") (pintype "passive"))
      (node (ref "R20") (pin "1") (pinfunction "1_1") (pintype "passive"))
      (node (ref "SW6") (pin "P$2") (pinfunction "S_P$2") (pintype "passive"))
      (node (ref "SW6") (pin "P$2.1") (pinfunction "S1_P$2.1") (pintype "passive"))
    )
    (net (code "52") (name "Net-(SW7-S)") (class "Default")
      (node (ref "C16") (pin "2") (pinfunction "2_2") (pintype "passive"))
      (node (ref "R25") (pin "1") (pinfunction "1_1") (pintype "passive"))
      (node (ref "SW7") (pin "P$2") (pinfunction "S_P$2") (pintype "passive"))
      (node (ref "SW7") (pin "P$2.1") (pinfunction "S1_P$2.1") (pintype "passive"))
    )
    (net (code "53") (name "Net-(SW8-S)") (class "Default")
      (node (ref "C17") (pin "2") (pinfunction "2_2") (pintype "passive"))
      (node (ref "R26") (pin "1") (pinfunction "1_1") (pintype "passive"))
      (node (ref "SW8") (pin "P$2") (pinfunction "S_P$2") (pintype "passive"))
      (node (ref "SW8") (pin "P$2.1") (pinfunction "S1_P$2.1") (pintype "passive"))
    )
    (net (code "54") (name "Net-(U1-CBUS1)") (class "Default")
      (node (ref "RX") (pin "C") (pinfunction "C_C") (pintype "passive"))
      (node (ref "U1") (pin "17") (pinfunction "CBUS1_17") (pintype "bidirectional"))
    )
    (net (code "55") (name "Net-(U1-CBUS2)") (class "Default")
      (node (ref "TX") (pin "C") (pinfunction "C_C") (pintype "passive"))
      (node (ref "U1") (pin "10") (pinfunction "CBUS2_10") (pintype "bidirectional"))
    )
    (net (code "56") (name "Net-(U1-USBDM)") (class "Default")
      (node (ref "R11") (pin "1") (pinfunction "1_1") (pintype "passive"))
      (node (ref "U1") (pin "12") (pinfunction "USBDM_12") (pintype "bidirectional"))
    )
    (net (code "57") (name "Net-(U1-USBDP)") (class "Default")
      (node (ref "R12") (pin "1") (pinfunction "1_1") (pintype "passive"))
      (node (ref "U1") (pin "11") (pinfunction "USBDP_11") (pintype "bidirectional"))
    )
    (net (code "58") (name "Net-(USB1-D+)") (class "Default")
      (node (ref "C9") (pin "1") (pinfunction "1_1") (pintype "passive"))
      (node (ref "R12") (pin "2") (pinfunction "2_2") (pintype "passive"))
      (node (ref "USB1") (pin "3") (pinfunction "D+_3") (pintype "bidirectional"))
    )
    (net (code "59") (name "Net-(USB1-D-)") (class "Default")
      (node (ref "C11") (pin "1") (pinfunction "1_1") (pintype "passive"))
      (node (ref "R11") (pin "2") (pinfunction "2_2") (pintype "passive"))
      (node (ref "USB1") (pin "2") (pinfunction "D-_2") (pintype "bidirectional"))
    )
    (net (code "60") (name "unconnected-(J7-Pad2)") (class "Default")
      (node (ref "J7") (pin "2") (pinfunction "2_2") (pintype "passive"))
    )
    (net (code "61") (name "unconnected-(LED6-DO-Pad2-DOUT)") (class "Default")
      (node (ref "LED6") (pin "2-DOUT") (pinfunction "DO_2-DOUT") (pintype "output"))
    )
    (net (code "62") (name "unconnected-(U1-CBUS0-Pad18)") (class "Default")
      (node (ref "U1") (pin "18") (pinfunction "CBUS0_18") (pintype "bidirectional"))
    )
    (net (code "63") (name "unconnected-(U1-CBUS3-Pad19)") (class "Default")
      (node (ref "U1") (pin "19") (pinfunction "CBUS3_19") (pintype "bidirectional"))
    )
    (net (code "64") (name "unconnected-(U1-~{CTS}-Pad9)") (class "Default")
      (node (ref "U1") (pin "9") (pinfunction "~{CTS}_9") (pintype "bidirectional"))
    )
    (net (code "65") (name "unconnected-(U1-~{DCD}-Pad8)") (class "Default")
      (node (ref "U1") (pin "8") (pinfunction "~{DCD}_8") (pintype "bidirectional"))
    )
    (net (code "66") (name "unconnected-(U1-~{DSR}-Pad7)") (class "Default")
      (node (ref "U1") (pin "7") (pinfunction "~{DSR}_7") (pintype "bidirectional"))
    )
    (net (code "67") (name "unconnected-(U1-~{RI}-Pad5)") (class "Default")
      (node (ref "U1") (pin "5") (pinfunction "~{RI}_5") (pintype "bidirectional"))
    )
    (net (code "68") (name "unconnected-(U2-CLK-Pad20)") (class "Default")
      (node (ref "U2") (pin "20") (pinfunction "CLK_20") (pintype "bidirectional"))
    )
    (net (code "69") (name "unconnected-(U2-CMD-Pad19)") (class "Default")
      (node (ref "U2") (pin "19") (pinfunction "CMD_19") (pintype "bidirectional"))
    )
    (net (code "70") (name "unconnected-(U2-IO2-Pad24)") (class "Default")
      (node (ref "U2") (pin "24") (pinfunction "IO2_24") (pintype "bidirectional"))
    )
    (net (code "71") (name "unconnected-(U2-IO4-Pad26)") (class "Default")
      (node (ref "U2") (pin "26") (pinfunction "IO4_26") (pintype "bidirectional"))
    )
    (net (code "72") (name "unconnected-(U2-IO12-Pad14)") (class "Default")
      (node (ref "U2") (pin "14") (pinfunction "IO12_14") (pintype "bidirectional"))
    )
    (net (code "73") (name "unconnected-(U2-IO15-Pad23)") (class "Default")
      (node (ref "U2") (pin "23") (pinfunction "IO15_23") (pintype "bidirectional"))
    )
    (net (code "74") (name "unconnected-(U2-NC-Pad32)") (class "Default")
      (node (ref "U2") (pin "32") (pinfunction "NC_32") (pintype "bidirectional"))
    )
    (net (code "75") (name "unconnected-(U2-SD1-Pad22)") (class "Default")
      (node (ref "U2") (pin "22") (pinfunction "SD1_22") (pintype "bidirectional"))
    )
    (net (code "76") (name "unconnected-(U2-SD2-Pad17)") (class "Default")
      (node (ref "U2") (pin "17") (pinfunction "SD2_17") (pintype "bidirectional"))
    )
    (net (code "77") (name "unconnected-(U2-SD3-Pad18)") (class "Default")
      (node (ref "U2") (pin "18") (pinfunction "SD3_18") (pintype "bidirectional"))
    )
    (net (code "78") (name "unconnected-(U2-SDO-Pad21)") (class "Default")
      (node (ref "U2") (pin "21") (pinfunction "SDO_21") (pintype "bidirectional"))
    )
    (net (code "79") (name "unconnected-(U2-SENSOR_VN-Pad5)") (class "Default")
      (node (ref "U2") (pin "5") (pinfunction "SENSOR_VN_5") (pintype "input"))
    )
    (net (code "80") (name "unconnected-(U2-SENSOR_VP-Pad4)") (class "Default")
      (node (ref "U2") (pin "4") (pinfunction "SENSOR_VP_4") (pintype "input"))
    )
    (net (code "81") (name "unconnected-(USB1-ID-Pad4)") (class "Default")
      (node (ref "USB1") (pin "4") (pinfunction "ID_4") (pintype "bidirectional"))
    )
  )
)
